# 12-5Convertor.net
KiCad netlist of a schematic drawn in EAGLE
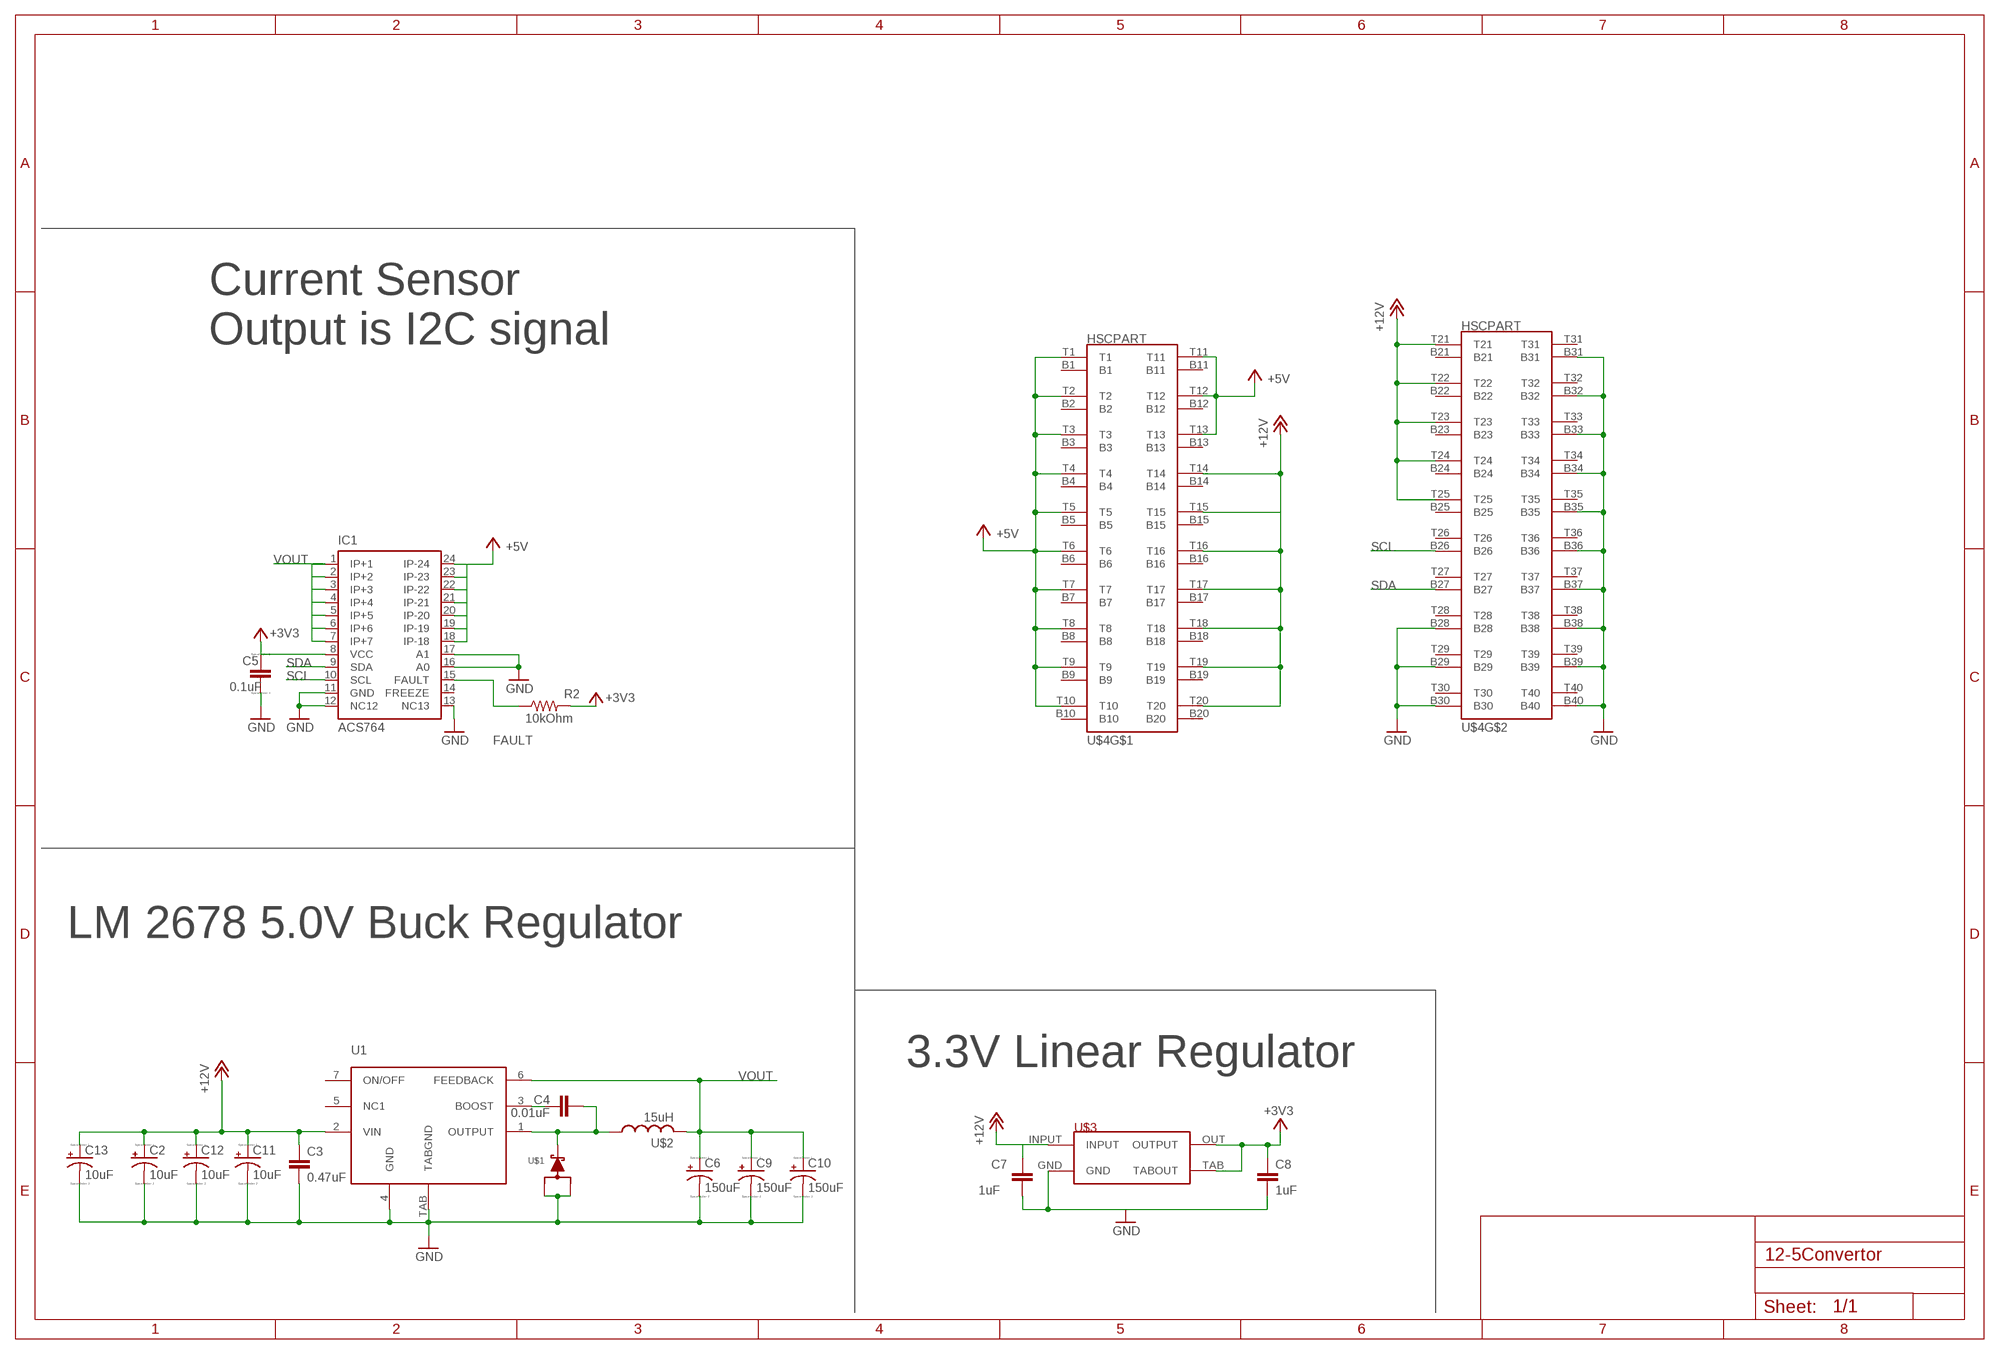
[diagram p0: schematic, sheet 1]

(export (version "E")
  (design (tool "Eeschema 10.0.6"))
  (components
    (comp (ref "C2")
      (value "10uF")
      (footprint "eagle-import:CTAN(7.30_4.30MM)")
      (libsource (lib "eagle-import") (part "C-TANTALUM(10UF_150UF)"))
    )
    (comp (ref "C3")
      (value "0.47uF")
      (footprint "eagle-import:0805")
      (libsource (lib "eagle-import") (part "CAP0805"))
    )
    (comp (ref "C4")
      (value "0.01uF")
      (footprint "eagle-import:0603-CAP")
      (libsource (lib "eagle-import") (part "SparkFun-Passives_CAP0603-CAP"))
    )
    (comp (ref "C5")
      (value "0.1uF")
      (footprint "eagle-import:C0603")
      (libsource (lib "eagle-import") (part "CC0603"))
    )
    (comp (ref "C6")
      (value "150uF")
      (footprint "eagle-import:CTAN(7.30_4.30MM)")
      (libsource (lib "eagle-import") (part "C-TANTALUM(10UF_150UF)"))
    )
    (comp (ref "C7")
      (value "1uF")
      (footprint "eagle-import:0603-CAP")
      (libsource (lib "eagle-import") (part "SparkFun-Passives_CAP0603-CAP"))
    )
    (comp (ref "C8")
      (value "1uF")
      (footprint "eagle-import:0603-CAP")
      (libsource (lib "eagle-import") (part "SparkFun-Passives_CAP0603-CAP"))
    )
    (comp (ref "C9")
      (value "150uF")
      (footprint "eagle-import:CTAN(7.30_4.30MM)")
      (libsource (lib "eagle-import") (part "C-TANTALUM(10UF_150UF)"))
    )
    (comp (ref "C10")
      (value "150uF")
      (footprint "eagle-import:CTAN(7.30_4.30MM)")
      (libsource (lib "eagle-import") (part "C-TANTALUM(10UF_150UF)"))
    )
    (comp (ref "C11")
      (value "10uF")
      (footprint "eagle-import:CTAN(7.30_4.30MM)")
      (libsource (lib "eagle-import") (part "C-TANTALUM(10UF_150UF)"))
    )
    (comp (ref "C12")
      (value "10uF")
      (footprint "eagle-import:CTAN(7.30_4.30MM)")
      (libsource (lib "eagle-import") (part "C-TANTALUM(10UF_150UF)"))
    )
    (comp (ref "C13")
      (value "10uF")
      (footprint "eagle-import:CTAN(7.30_4.30MM)")
      (libsource (lib "eagle-import") (part "C-TANTALUM(10UF_150UF)"))
    )
    (comp (ref "IC1")
      (value "ACS764")
      (footprint "eagle-import:SSOP24")
      (libsource (lib "eagle-import") (part "ACS764"))
    )
    (comp (ref "R2")
      (value "10kOhm")
      (footprint "eagle-import:R0603")
      (libsource (lib "eagle-import") (part "R-US_R0603"))
    )
    (comp (ref "U$1")
      (value "SWITCHMODE_SCHOTTKY")
      (footprint "eagle-import:DPAK-3")
      (libsource (lib "eagle-import") (part "SWITCHMODE_SCHOTTKY"))
    )
    (comp (ref "U$2")
      (value "15uH")
      (footprint "eagle-import:HCMA1305")
      (libsource (lib "eagle-import") (part "HCMA1305"))
    )
    (comp (ref "U$3")
      (value "NCP1117")
      (footprint "eagle-import:NCP1117")
      (libsource (lib "eagle-import") (part "NCP1117"))
    )
    (comp (ref "U$4")
      (value "HSCPART")
      (footprint "eagle-import:HSC8-40PINOUUT")
      (libsource (lib "eagle-import") (part "HSCPART"))
    )
    (comp (ref "U1")
      (value "LM2678")
      (footprint "eagle-import:LM2678")
      (libsource (lib "eagle-import") (part "LM2678"))
    )
  )
  (nets
    (net (code "1") (name "+3V3") (class "Default")
      (node (ref "C5") (pin "1") (pinfunction "1_1") (pintype "passive"))
      (node (ref "C8") (pin "1") (pinfunction "1_1") (pintype "passive"))
      (node (ref "IC1") (pin "8") (pinfunction "VCC_8") (pintype "bidirectional"))
      (node (ref "R2") (pin "2") (pinfunction "2_2") (pintype "passive"))
      (node (ref "U$3") (pin "OUT") (pinfunction "OUTPUT_OUT") (pintype "bidirectional"))
      (node (ref "U$3") (pin "TAB") (pinfunction "TABOUT_TAB") (pintype "bidirectional"))
    )
    (net (code "2") (name "+5V") (class "Default")
      (node (ref "IC1") (pin "18") (pinfunction "IP-18_18") (pintype "bidirectional"))
      (node (ref "IC1") (pin "19") (pinfunction "IP-19_19") (pintype "bidirectional"))
      (node (ref "IC1") (pin "20") (pinfunction "IP-20_20") (pintype "bidirectional"))
      (node (ref "IC1") (pin "21") (pinfunction "IP-21_21") (pintype "bidirectional"))
      (node (ref "IC1") (pin "22") (pinfunction "IP-22_22") (pintype "bidirectional"))
      (node (ref "IC1") (pin "23") (pinfunction "IP-23_23") (pintype "bidirectional"))
      (node (ref "IC1") (pin "24") (pinfunction "IP-24_24") (pintype "bidirectional"))
      (node (ref "U$4") (pin "T1") (pinfunction "T1_T1") (pintype "bidirectional"))
      (node (ref "U$4") (pin "T10") (pinfunction "T10_T10") (pintype "bidirectional"))
      (node (ref "U$4") (pin "T11") (pinfunction "T11_T11") (pintype "bidirectional"))
      (node (ref "U$4") (pin "T12") (pinfunction "T12_T12") (pintype "bidirectional"))
      (node (ref "U$4") (pin "T13") (pinfunction "T13_T13") (pintype "bidirectional"))
      (node (ref "U$4") (pin "T2") (pinfunction "T2_T2") (pintype "bidirectional"))
      (node (ref "U$4") (pin "T3") (pinfunction "T3_T3") (pintype "bidirectional"))
      (node (ref "U$4") (pin "T4") (pinfunction "T4_T4") (pintype "bidirectional"))
      (node (ref "U$4") (pin "T5") (pinfunction "T5_T5") (pintype "bidirectional"))
      (node (ref "U$4") (pin "T6") (pinfunction "T6_T6") (pintype "bidirectional"))
      (node (ref "U$4") (pin "T7") (pinfunction "T7_T7") (pintype "bidirectional"))
      (node (ref "U$4") (pin "T8") (pinfunction "T8_T8") (pintype "bidirectional"))
      (node (ref "U$4") (pin "T9") (pinfunction "T9_T9") (pintype "bidirectional"))
    )
    (net (code "3") (name "+12V") (class "Default")
      (node (ref "C11") (pin "+") (pinfunction "+_+") (pintype "passive"))
      (node (ref "C12") (pin "+") (pinfunction "+_+") (pintype "passive"))
      (node (ref "C13") (pin "+") (pinfunction "+_+") (pintype "passive"))
      (node (ref "C2") (pin "+") (pinfunction "+_+") (pintype "passive"))
      (node (ref "C3") (pin "1") (pinfunction "1_1") (pintype "passive"))
      (node (ref "C7") (pin "1") (pinfunction "1_1") (pintype "passive"))
      (node (ref "U$3") (pin "INPUT") (pinfunction "INPUT_INPUT") (pintype "bidirectional"))
      (node (ref "U$4") (pin "T14") (pinfunction "T14_T14") (pintype "bidirectional"))
      (node (ref "U$4") (pin "T15") (pinfunction "T15_T15") (pintype "bidirectional"))
      (node (ref "U$4") (pin "T16") (pinfunction "T16_T16") (pintype "bidirectional"))
      (node (ref "U$4") (pin "T17") (pinfunction "T17_T17") (pintype "bidirectional"))
      (node (ref "U$4") (pin "T18") (pinfunction "T18_T18") (pintype "bidirectional"))
      (node (ref "U$4") (pin "T19") (pinfunction "T19_T19") (pintype "bidirectional"))
      (node (ref "U$4") (pin "T20") (pinfunction "T20_T20") (pintype "bidirectional"))
      (node (ref "U$4") (pin "T21") (pinfunction "T21_T21") (pintype "bidirectional"))
      (node (ref "U$4") (pin "T22") (pinfunction "T22_T22") (pintype "bidirectional"))
      (node (ref "U$4") (pin "T23") (pinfunction "T23_T23") (pintype "bidirectional"))
      (node (ref "U$4") (pin "T24") (pinfunction "T24_T24") (pintype "bidirectional"))
      (node (ref "U$4") (pin "T25") (pinfunction "T25_T25") (pintype "bidirectional"))
      (node (ref "U1") (pin "2") (pinfunction "VIN_2") (pintype "bidirectional"))
    )
    (net (code "4") (name "/FAULT") (class "Default")
      (node (ref "IC1") (pin "15") (pinfunction "FAULT_15") (pintype "bidirectional"))
      (node (ref "R2") (pin "1") (pinfunction "1_1") (pintype "passive"))
    )
    (net (code "5") (name "/SCL") (class "Default")
      (node (ref "IC1") (pin "10") (pinfunction "SCL_10") (pintype "bidirectional"))
      (node (ref "U$4") (pin "B26") (pinfunction "B26_B26") (pintype "bidirectional"))
    )
    (net (code "6") (name "/SDA") (class "Default")
      (node (ref "IC1") (pin "9") (pinfunction "SDA_9") (pintype "bidirectional"))
      (node (ref "U$4") (pin "B27") (pinfunction "B27_B27") (pintype "bidirectional"))
    )
    (net (code "7") (name "/VOUT") (class "Default")
      (node (ref "C10") (pin "+") (pinfunction "+_+") (pintype "passive"))
      (node (ref "C6") (pin "+") (pinfunction "+_+") (pintype "passive"))
      (node (ref "C9") (pin "+") (pinfunction "+_+") (pintype "passive"))
      (node (ref "IC1") (pin "1") (pinfunction "IP+1_1") (pintype "bidirectional"))
      (node (ref "IC1") (pin "2") (pinfunction "IP+2_2") (pintype "bidirectional"))
      (node (ref "IC1") (pin "3") (pinfunction "IP+3_3") (pintype "bidirectional"))
      (node (ref "IC1") (pin "4") (pinfunction "IP+4_4") (pintype "bidirectional"))
      (node (ref "IC1") (pin "5") (pinfunction "IP+5_5") (pintype "bidirectional"))
      (node (ref "IC1") (pin "6") (pinfunction "IP+6_6") (pintype "bidirectional"))
      (node (ref "IC1") (pin "7") (pinfunction "IP+7_7") (pintype "bidirectional"))
      (node (ref "U$2") (pin "P$2") (pinfunction "2_P$2") (pintype "passive"))
      (node (ref "U1") (pin "6") (pinfunction "FEEDBACK_6") (pintype "bidirectional"))
    )
    (net (code "8") (name "GND") (class "Default")
      (node (ref "C10") (pin "-") (pinfunction "-_-") (pintype "passive"))
      (node (ref "C11") (pin "-") (pinfunction "-_-") (pintype "passive"))
      (node (ref "C12") (pin "-") (pinfunction "-_-") (pintype "passive"))
      (node (ref "C13") (pin "-") (pinfunction "-_-") (pintype "passive"))
      (node (ref "C2") (pin "-") (pinfunction "-_-") (pintype "passive"))
      (node (ref "C3") (pin "2") (pinfunction "2_2") (pintype "passive"))
      (node (ref "C5") (pin "2") (pinfunction "2_2") (pintype "passive"))
      (node (ref "C6") (pin "-") (pinfunction "-_-") (pintype "passive"))
      (node (ref "C7") (pin "2") (pinfunction "2_2") (pintype "passive"))
      (node (ref "C8") (pin "2") (pinfunction "2_2") (pintype "passive"))
      (node (ref "C9") (pin "-") (pinfunction "-_-") (pintype "passive"))
      (node (ref "IC1") (pin "11") (pinfunction "GND_11") (pintype "bidirectional"))
      (node (ref "IC1") (pin "12") (pinfunction "NC12_12") (pintype "bidirectional"))
      (node (ref "IC1") (pin "13") (pinfunction "NC13_13") (pintype "bidirectional"))
      (node (ref "IC1") (pin "16") (pinfunction "A0_16") (pintype "bidirectional"))
      (node (ref "IC1") (pin "17") (pinfunction "A1_17") (pintype "bidirectional"))
      (node (ref "U$1") (pin "P$1") (pinfunction "P$1_P$1") (pintype "bidirectional"))
      (node (ref "U$1") (pin "P$3") (pinfunction "P$3_P$3") (pintype "bidirectional"))
      (node (ref "U$3") (pin "GND") (pinfunction "GND_GND") (pintype "bidirectional"))
      (node (ref "U$4") (pin "B28") (pinfunction "B28_B28") (pintype "bidirectional"))
      (node (ref "U$4") (pin "B29") (pinfunction "B29_B29") (pintype "bidirectional"))
      (node (ref "U$4") (pin "B30") (pinfunction "B30_B30") (pintype "bidirectional"))
      (node (ref "U$4") (pin "B31") (pinfunction "B31_B31") (pintype "bidirectional"))
      (node (ref "U$4") (pin "B32") (pinfunction "B32_B32") (pintype "bidirectional"))
      (node (ref "U$4") (pin "B33") (pinfunction "B33_B33") (pintype "bidirectional"))
      (node (ref "U$4") (pin "B34") (pinfunction "B34_B34") (pintype "bidirectional"))
      (node (ref "U$4") (pin "B35") (pinfunction "B35_B35") (pintype "bidirectional"))
      (node (ref "U$4") (pin "B36") (pinfunction "B36_B36") (pintype "bidirectional"))
      (node (ref "U$4") (pin "B37") (pinfunction "B37_B37") (pintype "bidirectional"))
      (node (ref "U$4") (pin "B38") (pinfunction "B38_B38") (pintype "bidirectional"))
      (node (ref "U$4") (pin "B39") (pinfunction "B39_B39") (pintype "bidirectional"))
      (node (ref "U$4") (pin "B40") (pinfunction "B40_B40") (pintype "bidirectional"))
      (node (ref "U1") (pin "4") (pinfunction "GND_4") (pintype "bidirectional"))
      (node (ref "U1") (pin "TAB") (pinfunction "TABGND_TAB") (pintype "bidirectional"))
    )
    (net (code "9") (name "Net-(U$2-1)") (class "Default")
      (node (ref "C4") (pin "2") (pinfunction "2_2") (pintype "passive"))
      (node (ref "U$1") (pin "P$4") (pinfunction "P$4_P$4") (pintype "bidirectional"))
      (node (ref "U$2") (pin "P$1") (pinfunction "1_P$1") (pintype "passive"))
      (node (ref "U1") (pin "1") (pinfunction "OUTPUT_1") (pintype "bidirectional"))
    )
    (net (code "10") (name "Net-(U1-BOOST)") (class "Default")
      (node (ref "C4") (pin "1") (pinfunction "1_1") (pintype "passive"))
      (node (ref "U1") (pin "3") (pinfunction "BOOST_3") (pintype "bidirectional"))
    )
    (net (code "11") (name "unconnected-(IC1-FREEZE-Pad14)") (class "Default")
      (node (ref "IC1") (pin "14") (pinfunction "FREEZE_14") (pintype "bidirectional"))
    )
    (net (code "12") (name "unconnected-(U$4-PadB1)") (class "Default")
      (node (ref "U$4") (pin "B1") (pinfunction "B1_B1") (pintype "bidirectional"))
    )
    (net (code "13") (name "unconnected-(U$4-PadB2)") (class "Default")
      (node (ref "U$4") (pin "B2") (pinfunction "B2_B2") (pintype "bidirectional"))
    )
    (net (code "14") (name "unconnected-(U$4-PadB3)") (class "Default")
      (node (ref "U$4") (pin "B3") (pinfunction "B3_B3") (pintype "bidirectional"))
    )
    (net (code "15") (name "unconnected-(U$4-PadB4)") (class "Default")
      (node (ref "U$4") (pin "B4") (pinfunction "B4_B4") (pintype "bidirectional"))
    )
    (net (code "16") (name "unconnected-(U$4-PadB5)") (class "Default")
      (node (ref "U$4") (pin "B5") (pinfunction "B5_B5") (pintype "bidirectional"))
    )
    (net (code "17") (name "unconnected-(U$4-PadB6)") (class "Default")
      (node (ref "U$4") (pin "B6") (pinfunction "B6_B6") (pintype "bidirectional"))
    )
    (net (code "18") (name "unconnected-(U$4-PadB7)") (class "Default")
      (node (ref "U$4") (pin "B7") (pinfunction "B7_B7") (pintype "bidirectional"))
    )
    (net (code "19") (name "unconnected-(U$4-PadB8)") (class "Default")
      (node (ref "U$4") (pin "B8") (pinfunction "B8_B8") (pintype "bidirectional"))
    )
    (net (code "20") (name "unconnected-(U$4-PadB9)") (class "Default")
      (node (ref "U$4") (pin "B9") (pinfunction "B9_B9") (pintype "bidirectional"))
    )
    (net (code "21") (name "unconnected-(U$4-PadB10)") (class "Default")
      (node (ref "U$4") (pin "B10") (pinfunction "B10_B10") (pintype "bidirectional"))
    )
    (net (code "22") (name "unconnected-(U$4-PadB11)") (class "Default")
      (node (ref "U$4") (pin "B11") (pinfunction "B11_B11") (pintype "bidirectional"))
    )
    (net (code "23") (name "unconnected-(U$4-PadB12)") (class "Default")
      (node (ref "U$4") (pin "B12") (pinfunction "B12_B12") (pintype "bidirectional"))
    )
    (net (code "24") (name "unconnected-(U$4-PadB13)") (class "Default")
      (node (ref "U$4") (pin "B13") (pinfunction "B13_B13") (pintype "bidirectional"))
    )
    (net (code "25") (name "unconnected-(U$4-PadB14)") (class "Default")
      (node (ref "U$4") (pin "B14") (pinfunction "B14_B14") (pintype "bidirectional"))
    )
    (net (code "26") (name "unconnected-(U$4-PadB15)") (class "Default")
      (node (ref "U$4") (pin "B15") (pinfunction "B15_B15") (pintype "bidirectional"))
    )
    (net (code "27") (name "unconnected-(U$4-PadB16)") (class "Default")
      (node (ref "U$4") (pin "B16") (pinfunction "B16_B16") (pintype "bidirectional"))
    )
    (net (code "28") (name "unconnected-(U$4-PadB17)") (class "Default")
      (node (ref "U$4") (pin "B17") (pinfunction "B17_B17") (pintype "bidirectional"))
    )
    (net (code "29") (name "unconnected-(U$4-PadB18)") (class "Default")
      (node (ref "U$4") (pin "B18") (pinfunction "B18_B18") (pintype "bidirectional"))
    )
    (net (code "30") (name "unconnected-(U$4-PadB19)") (class "Default")
      (node (ref "U$4") (pin "B19") (pinfunction "B19_B19") (pintype "bidirectional"))
    )
    (net (code "31") (name "unconnected-(U$4-PadB20)") (class "Default")
      (node (ref "U$4") (pin "B20") (pinfunction "B20_B20") (pintype "bidirectional"))
    )
    (net (code "32") (name "unconnected-(U$4-PadB21)") (class "Default")
      (node (ref "U$4") (pin "B21") (pinfunction "B21_B21") (pintype "bidirectional"))
    )
    (net (code "33") (name "unconnected-(U$4-PadB22)") (class "Default")
      (node (ref "U$4") (pin "B22") (pinfunction "B22_B22") (pintype "bidirectional"))
    )
    (net (code "34") (name "unconnected-(U$4-PadB23)") (class "Default")
      (node (ref "U$4") (pin "B23") (pinfunction "B23_B23") (pintype "bidirectional"))
    )
    (net (code "35") (name "unconnected-(U$4-PadB24)") (class "Default")
      (node (ref "U$4") (pin "B24") (pinfunction "B24_B24") (pintype "bidirectional"))
    )
    (net (code "36") (name "unconnected-(U$4-PadB25)") (class "Default")
      (node (ref "U$4") (pin "B25") (pinfunction "B25_B25") (pintype "bidirectional"))
    )
    (net (code "37") (name "unconnected-(U$4-PadT26)") (class "Default")
      (node (ref "U$4") (pin "T26") (pinfunction "T26_T26") (pintype "bidirectional"))
    )
    (net (code "38") (name "unconnected-(U$4-PadT27)") (class "Default")
      (node (ref "U$4") (pin "T27") (pinfunction "T27_T27") (pintype "bidirectional"))
    )
    (net (code "39") (name "unconnected-(U$4-PadT28)") (class "Default")
      (node (ref "U$4") (pin "T28") (pinfunction "T28_T28") (pintype "bidirectional"))
    )
    (net (code "40") (name "unconnected-(U$4-PadT29)") (class "Default")
      (node (ref "U$4") (pin "T29") (pinfunction "T29_T29") (pintype "bidirectional"))
    )
    (net (code "41") (name "unconnected-(U$4-PadT30)") (class "Default")
      (node (ref "U$4") (pin "T30") (pinfunction "T30_T30") (pintype "bidirectional"))
    )
    (net (code "42") (name "unconnected-(U$4-PadT31)") (class "Default")
      (node (ref "U$4") (pin "T31") (pinfunction "T31_T31") (pintype "bidirectional"))
    )
    (net (code "43") (name "unconnected-(U$4-PadT32)") (class "Default")
      (node (ref "U$4") (pin "T32") (pinfunction "T32_T32") (pintype "bidirectional"))
    )
    (net (code "44") (name "unconnected-(U$4-PadT33)") (class "Default")
      (node (ref "U$4") (pin "T33") (pinfunction "T33_T33") (pintype "bidirectional"))
    )
    (net (code "45") (name "unconnected-(U$4-PadT34)") (class "Default")
      (node (ref "U$4") (pin "T34") (pinfunction "T34_T34") (pintype "bidirectional"))
    )
    (net (code "46") (name "unconnected-(U$4-PadT35)") (class "Default")
      (node (ref "U$4") (pin "T35") (pinfunction "T35_T35") (pintype "bidirectional"))
    )
    (net (code "47") (name "unconnected-(U$4-PadT36)") (class "Default")
      (node (ref "U$4") (pin "T36") (pinfunction "T36_T36") (pintype "bidirectional"))
    )
    (net (code "48") (name "unconnected-(U$4-PadT37)") (class "Default")
      (node (ref "U$4") (pin "T37") (pinfunction "T37_T37") (pintype "bidirectional"))
    )
    (net (code "49") (name "unconnected-(U$4-PadT38)") (class "Default")
      (node (ref "U$4") (pin "T38") (pinfunction "T38_T38") (pintype "bidirectional"))
    )
    (net (code "50") (name "unconnected-(U$4-PadT39)") (class "Default")
      (node (ref "U$4") (pin "T39") (pinfunction "T39_T39") (pintype "bidirectional"))
    )
    (net (code "51") (name "unconnected-(U$4-PadT40)") (class "Default")
      (node (ref "U$4") (pin "T40") (pinfunction "T40_T40") (pintype "bidirectional"))
    )
    (net (code "52") (name "unconnected-(U1-NC1-Pad5)") (class "Default")
      (node (ref "U1") (pin "5") (pinfunction "NC1_5") (pintype "no_connect"))
    )
    (net (code "53") (name "unconnected-(U1-ON{slash}OFF-Pad7)") (class "Default")
      (node (ref "U1") (pin "7") (pinfunction "ON/OFF_7") (pintype "bidirectional"))
    )
  )
)
